# stm32f4breakout.net
KiCad netlist of a schematic drawn in EAGLE
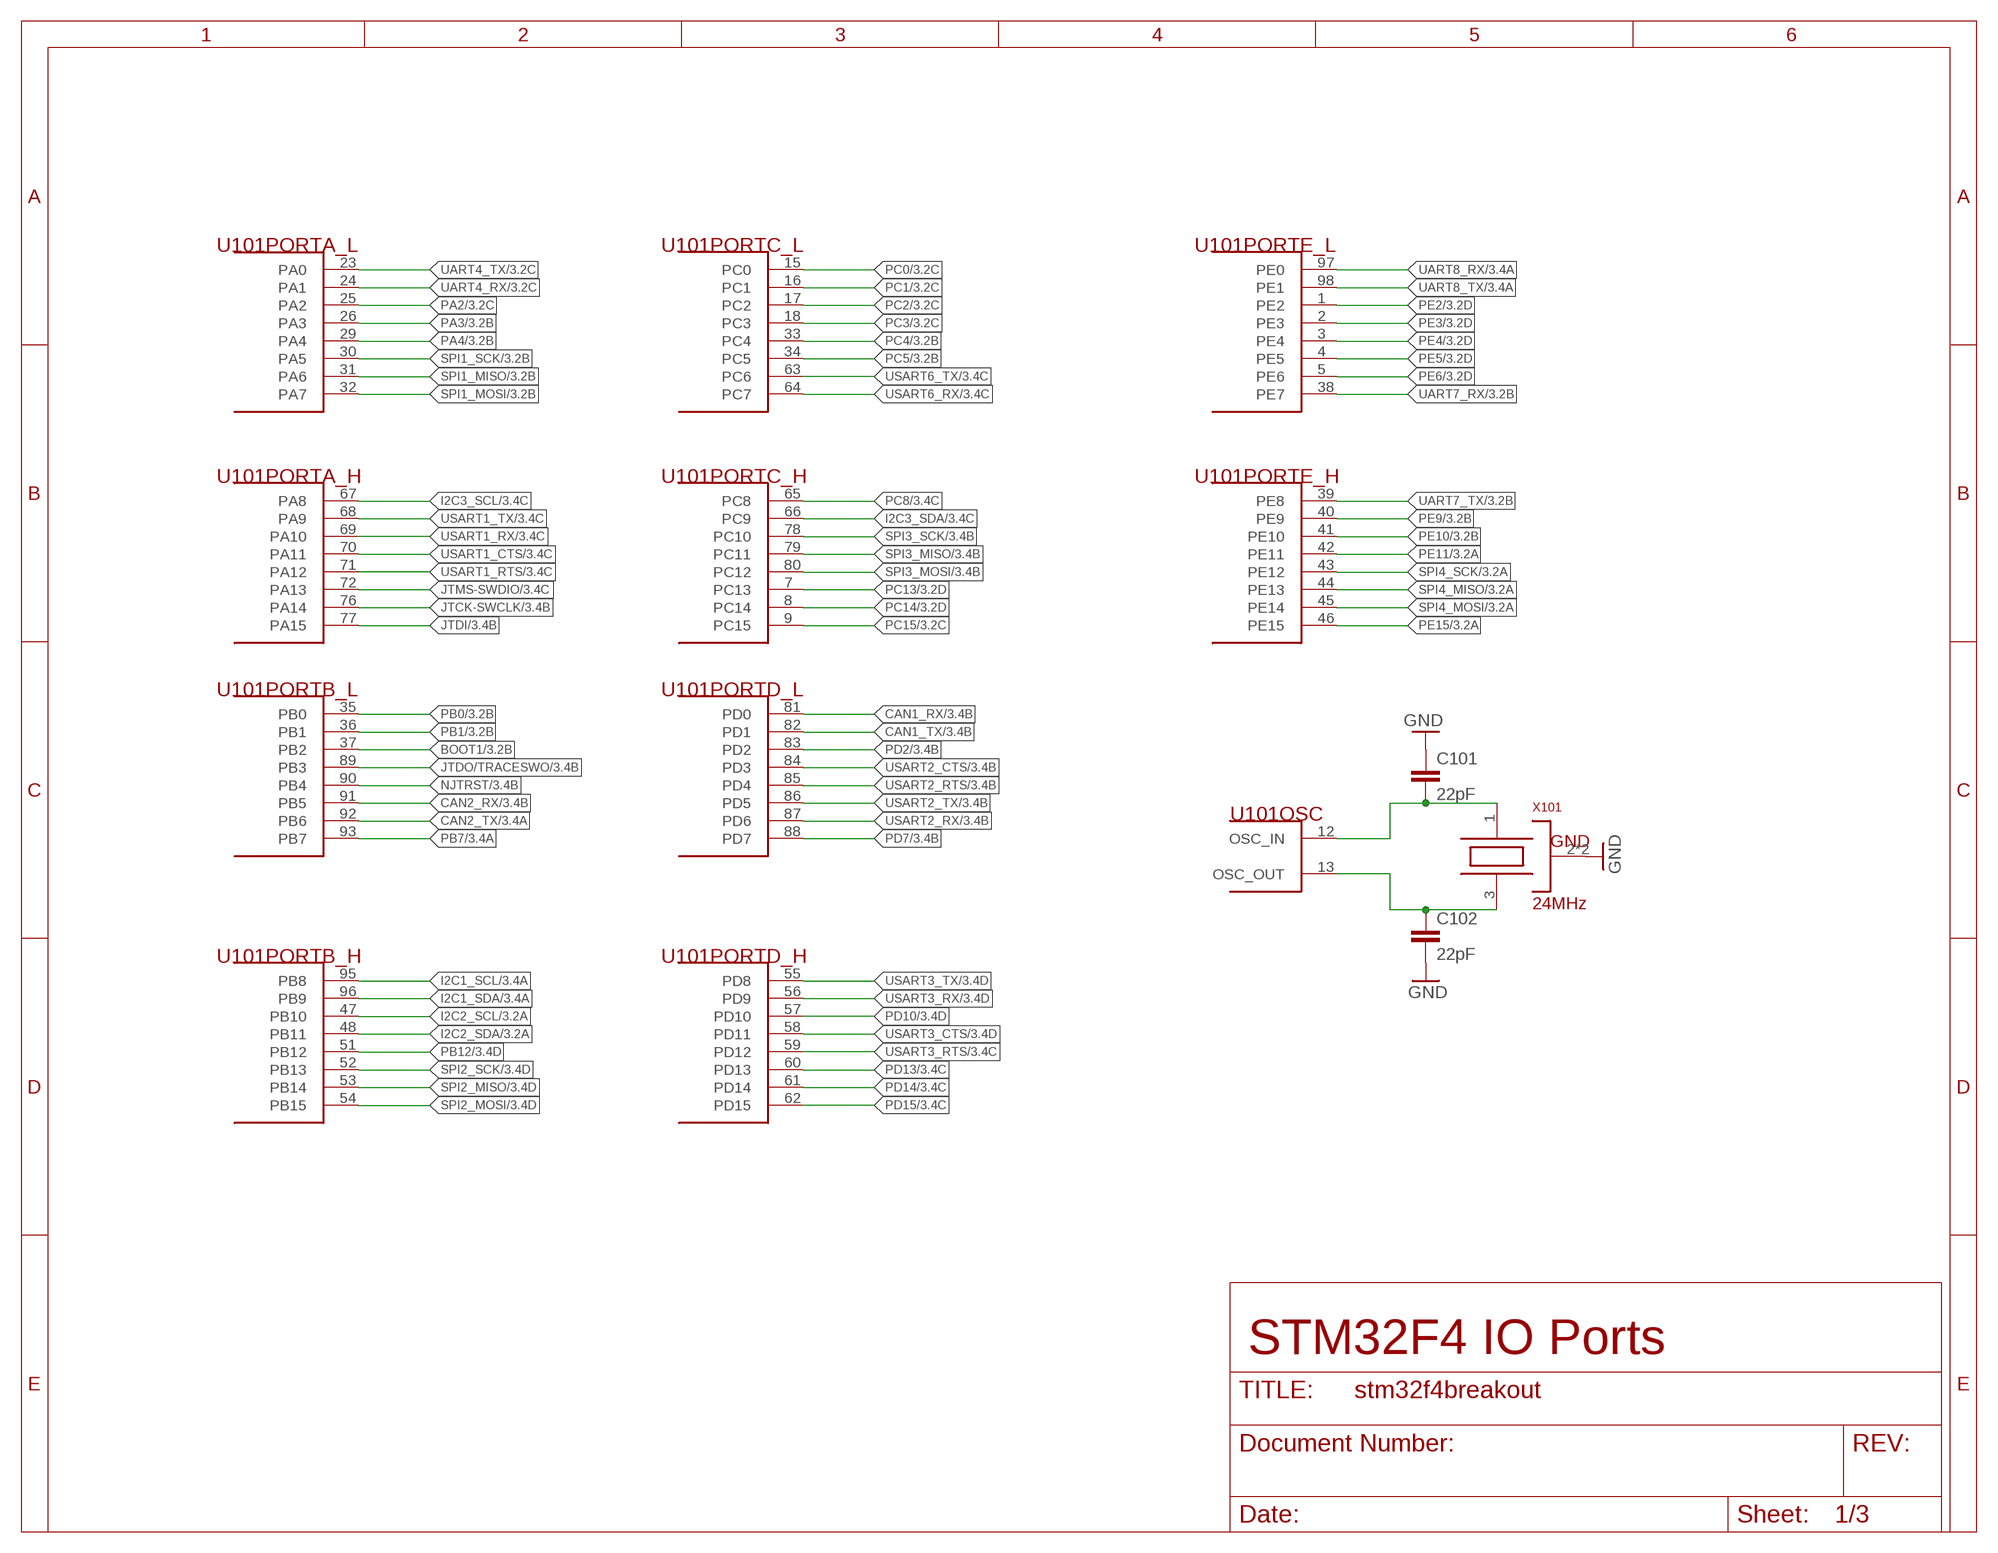
[diagram p0: schematic, sheet 1]
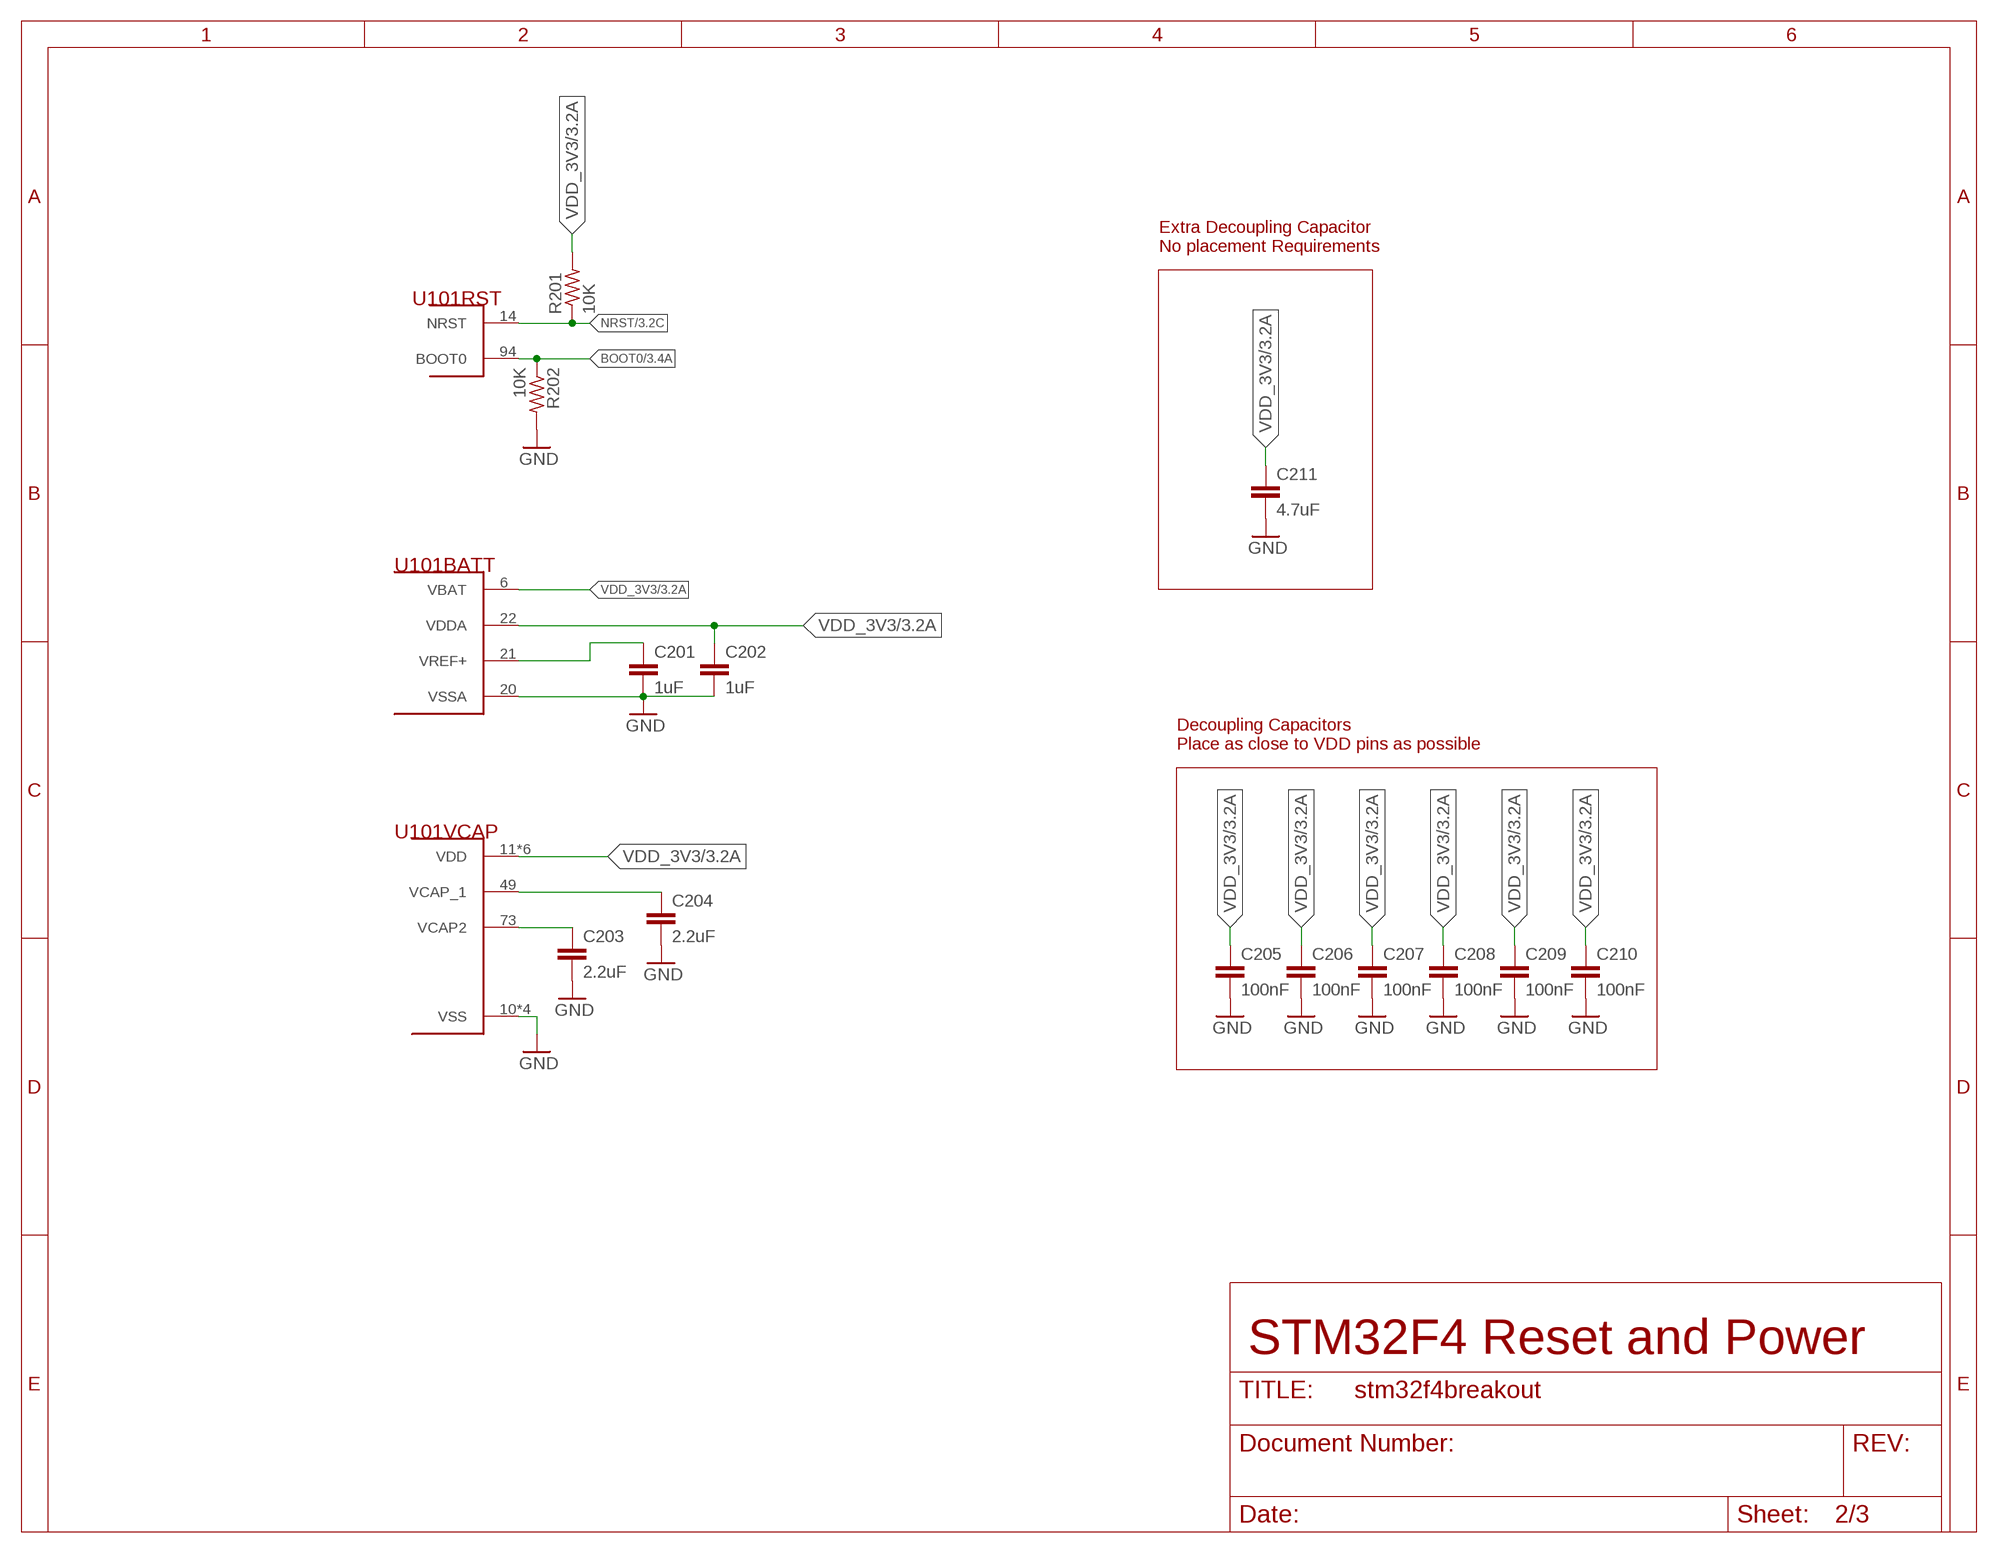
[diagram p1: schematic, sheet 2]
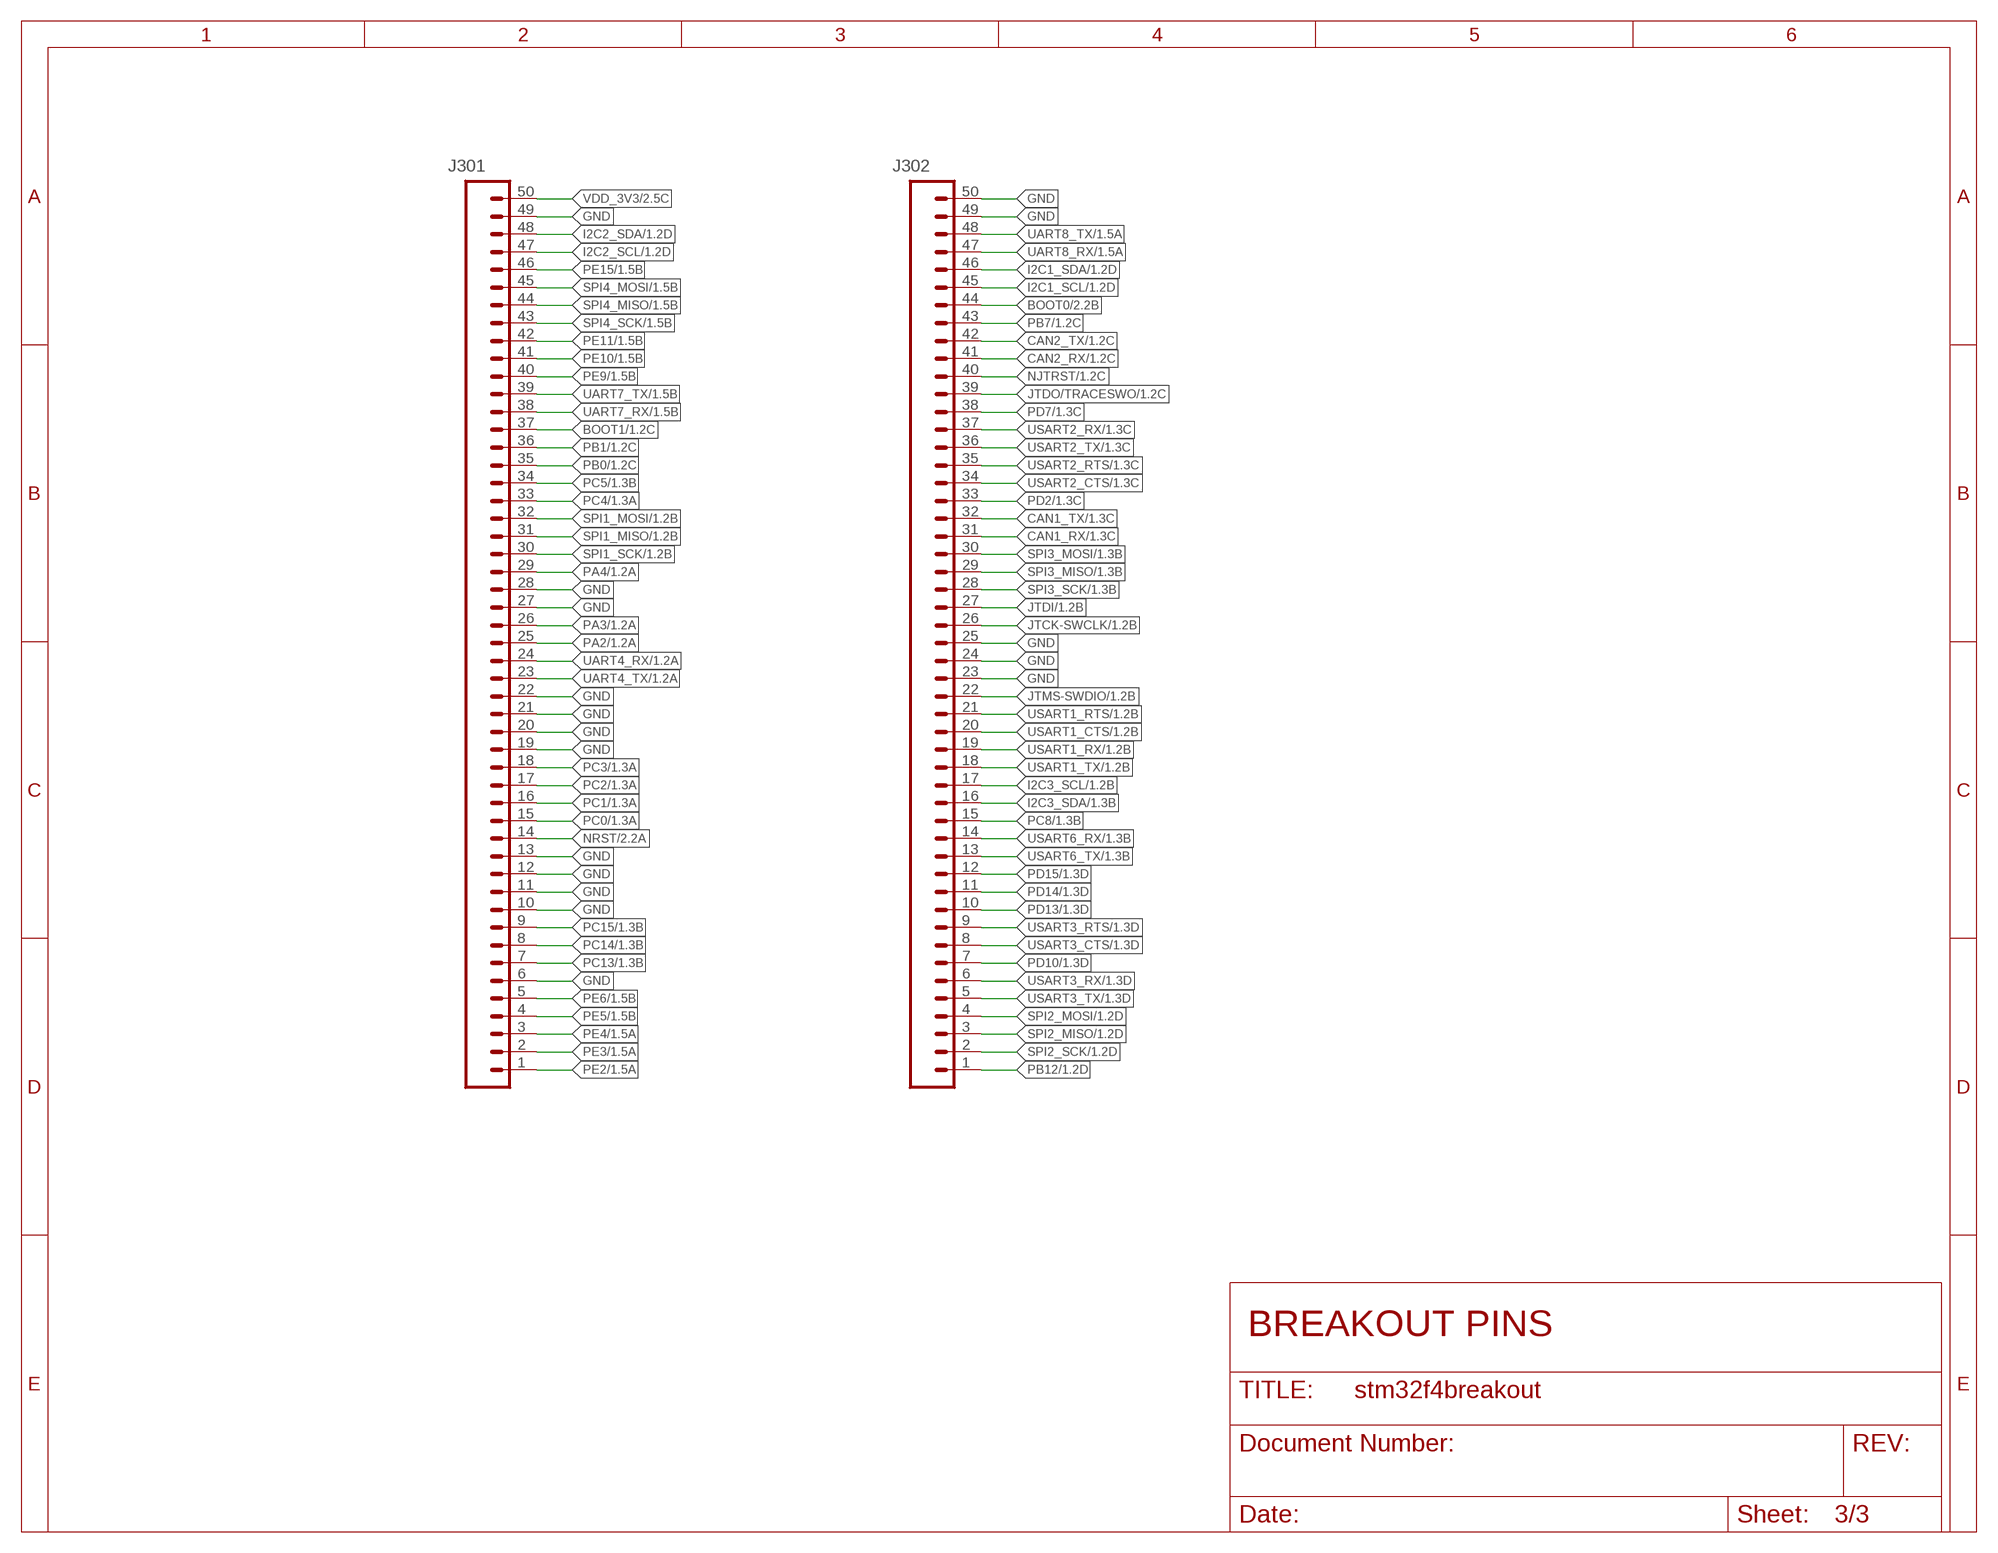
[diagram p2: schematic, sheet 3]

(export (version "E")
  (design (tool "Eeschema 10.0.6"))
  (components
    (comp (ref "C101")
      (value "22pF")
      (footprint "eagle-import:C0603")
      (libsource (lib "eagle-import") (part "C-EUC0603"))
    )
    (comp (ref "C102")
      (value "22pF")
      (footprint "eagle-import:C0603")
      (libsource (lib "eagle-import") (part "C-EUC0603"))
    )
    (comp (ref "U101")
      (value "STM32F427VGT6")
      (footprint "eagle-import:LQFP-100")
      (libsource (lib "eagle-import") (part "STM32F427VGT6"))
    )
    (comp (ref "X101")
      (value "24MHz")
      (footprint "eagle-import:OSC3.2X2.5")
      (libsource (lib "eagle-import") (part "OSCILLATOR"))
    )
    (comp (ref "C201")
      (value "1uF")
      (footprint "eagle-import:C0603")
      (libsource (lib "eagle-import") (part "C-EUC0603"))
    )
    (comp (ref "C202")
      (value "1uF")
      (footprint "eagle-import:C0603")
      (libsource (lib "eagle-import") (part "C-EUC0603"))
    )
    (comp (ref "C203")
      (value "2.2uF")
      (footprint "eagle-import:C0603")
      (libsource (lib "eagle-import") (part "C-EUC0603"))
    )
    (comp (ref "C204")
      (value "2.2uF")
      (footprint "eagle-import:C0603")
      (libsource (lib "eagle-import") (part "C-EUC0603"))
    )
    (comp (ref "C205")
      (value "100nF")
      (footprint "eagle-import:C0603")
      (libsource (lib "eagle-import") (part "C-EUC0603"))
    )
    (comp (ref "C206")
      (value "100nF")
      (footprint "eagle-import:C0603")
      (libsource (lib "eagle-import") (part "C-EUC0603"))
    )
    (comp (ref "C207")
      (value "100nF")
      (footprint "eagle-import:C0603")
      (libsource (lib "eagle-import") (part "C-EUC0603"))
    )
    (comp (ref "C208")
      (value "100nF")
      (footprint "eagle-import:C0603")
      (libsource (lib "eagle-import") (part "C-EUC0603"))
    )
    (comp (ref "C209")
      (value "100nF")
      (footprint "eagle-import:C0603")
      (libsource (lib "eagle-import") (part "C-EUC0603"))
    )
    (comp (ref "C210")
      (value "100nF")
      (footprint "eagle-import:C0603")
      (libsource (lib "eagle-import") (part "C-EUC0603"))
    )
    (comp (ref "C211")
      (value "4.7uF")
      (footprint "eagle-import:C0603")
      (libsource (lib "eagle-import") (part "C-EUC0603"))
    )
    (comp (ref "R201")
      (value "10K")
      (footprint "eagle-import:R0603")
      (libsource (lib "eagle-import") (part "R-US_R0603"))
    )
    (comp (ref "R202")
      (value "10K")
      (footprint "eagle-import:R0603")
      (libsource (lib "eagle-import") (part "R-US_R0603"))
    )
    (comp (ref "J301")
      (value "PINHD-1X50")
      (footprint "eagle-import:1X50")
      (libsource (lib "eagle-import") (part "PINHD-1X50"))
    )
    (comp (ref "J302")
      (value "PINHD-1X50")
      (footprint "eagle-import:1X50")
      (libsource (lib "eagle-import") (part "PINHD-1X50"))
    )
  )
  (nets
    (net (code "1") (name "BOOT0") (class "Default")
      (node (ref "J302") (pin "44") (pinfunction "44_44") (pintype "passive"))
      (node (ref "R202") (pin "1") (pinfunction "1_1") (pintype "passive"))
      (node (ref "U101") (pin "94") (pinfunction "BOOT0_94") (pintype "power_in"))
    )
    (net (code "2") (name "BOOT1") (class "Default")
      (node (ref "J301") (pin "37") (pinfunction "37_37") (pintype "passive"))
      (node (ref "U101") (pin "37") (pinfunction "PB2_37") (pintype "power_in"))
    )
    (net (code "3") (name "CAN1_RX") (class "Default")
      (node (ref "J302") (pin "31") (pinfunction "31_31") (pintype "passive"))
      (node (ref "U101") (pin "81") (pinfunction "PD0_81") (pintype "power_in"))
    )
    (net (code "4") (name "CAN1_TX") (class "Default")
      (node (ref "J302") (pin "32") (pinfunction "32_32") (pintype "passive"))
      (node (ref "U101") (pin "82") (pinfunction "PD1_82") (pintype "power_in"))
    )
    (net (code "5") (name "CAN2_RX") (class "Default")
      (node (ref "J302") (pin "41") (pinfunction "41_41") (pintype "passive"))
      (node (ref "U101") (pin "91") (pinfunction "PB5_91") (pintype "power_in"))
    )
    (net (code "6") (name "CAN2_TX") (class "Default")
      (node (ref "J302") (pin "42") (pinfunction "42_42") (pintype "passive"))
      (node (ref "U101") (pin "92") (pinfunction "PB6_92") (pintype "power_in"))
    )
    (net (code "7") (name "GND") (class "Default")
      (node (ref "C101") (pin "1") (pinfunction "1_1") (pintype "passive"))
      (node (ref "C102") (pin "2") (pinfunction "2_2") (pintype "passive"))
      (node (ref "C201") (pin "2") (pinfunction "2_2") (pintype "passive"))
      (node (ref "C202") (pin "2") (pinfunction "2_2") (pintype "passive"))
      (node (ref "C203") (pin "2") (pinfunction "2_2") (pintype "passive"))
      (node (ref "C204") (pin "2") (pinfunction "2_2") (pintype "passive"))
      (node (ref "C205") (pin "2") (pinfunction "2_2") (pintype "passive"))
      (node (ref "C206") (pin "2") (pinfunction "2_2") (pintype "passive"))
      (node (ref "C207") (pin "2") (pinfunction "2_2") (pintype "passive"))
      (node (ref "C208") (pin "2") (pinfunction "2_2") (pintype "passive"))
      (node (ref "C209") (pin "2") (pinfunction "2_2") (pintype "passive"))
      (node (ref "C210") (pin "2") (pinfunction "2_2") (pintype "passive"))
      (node (ref "C211") (pin "2") (pinfunction "2_2") (pintype "passive"))
      (node (ref "J301") (pin "10") (pinfunction "10_10") (pintype "passive"))
      (node (ref "J301") (pin "11") (pinfunction "11_11") (pintype "passive"))
      (node (ref "J301") (pin "12") (pinfunction "12_12") (pintype "passive"))
      (node (ref "J301") (pin "13") (pinfunction "13_13") (pintype "passive"))
      (node (ref "J301") (pin "19") (pinfunction "19_19") (pintype "passive"))
      (node (ref "J301") (pin "20") (pinfunction "20_20") (pintype "passive"))
      (node (ref "J301") (pin "21") (pinfunction "21_21") (pintype "passive"))
      (node (ref "J301") (pin "22") (pinfunction "22_22") (pintype "passive"))
      (node (ref "J301") (pin "27") (pinfunction "27_27") (pintype "passive"))
      (node (ref "J301") (pin "28") (pinfunction "28_28") (pintype "passive"))
      (node (ref "J301") (pin "49") (pinfunction "49_49") (pintype "passive"))
      (node (ref "J301") (pin "6") (pinfunction "6_6") (pintype "passive"))
      (node (ref "J302") (pin "23") (pinfunction "23_23") (pintype "passive"))
      (node (ref "J302") (pin "24") (pinfunction "24_24") (pintype "passive"))
      (node (ref "J302") (pin "25") (pinfunction "25_25") (pintype "passive"))
      (node (ref "J302") (pin "49") (pinfunction "49_49") (pintype "passive"))
      (node (ref "J302") (pin "50") (pinfunction "50_50") (pintype "passive"))
      (node (ref "R202") (pin "2") (pinfunction "2_2") (pintype "passive"))
      (node (ref "U101") (pin "10") (pinfunction "VSS_10") (pintype "power_in"))
      (node (ref "U101") (pin "20") (pinfunction "VSSA_20") (pintype "power_in"))
      (node (ref "U101") (pin "27") (pinfunction "VSS_27") (pintype "power_in"))
      (node (ref "U101") (pin "74") (pinfunction "VSS_74") (pintype "power_in"))
      (node (ref "U101") (pin "99") (pinfunction "VSS_99") (pintype "power_in"))
      (node (ref "X101") (pin "2") (pinfunction "GND_2") (pintype "power_in"))
      (node (ref "X101") (pin "4") (pinfunction "GND_4") (pintype "power_in"))
    )
    (net (code "8") (name "I2C1_SCL") (class "Default")
      (node (ref "J302") (pin "45") (pinfunction "45_45") (pintype "passive"))
      (node (ref "U101") (pin "95") (pinfunction "PB8_95") (pintype "power_in"))
    )
    (net (code "9") (name "I2C1_SDA") (class "Default")
      (node (ref "J302") (pin "46") (pinfunction "46_46") (pintype "passive"))
      (node (ref "U101") (pin "96") (pinfunction "PB9_96") (pintype "power_in"))
    )
    (net (code "10") (name "I2C2_SCL") (class "Default")
      (node (ref "J301") (pin "47") (pinfunction "47_47") (pintype "passive"))
      (node (ref "U101") (pin "47") (pinfunction "PB10_47") (pintype "power_in"))
    )
    (net (code "11") (name "I2C2_SDA") (class "Default")
      (node (ref "J301") (pin "48") (pinfunction "48_48") (pintype "passive"))
      (node (ref "U101") (pin "48") (pinfunction "PB11_48") (pintype "power_in"))
    )
    (net (code "12") (name "I2C3_SCL") (class "Default")
      (node (ref "J302") (pin "17") (pinfunction "17_17") (pintype "passive"))
      (node (ref "U101") (pin "67") (pinfunction "PA8_67") (pintype "power_in"))
    )
    (net (code "13") (name "I2C3_SDA") (class "Default")
      (node (ref "J302") (pin "16") (pinfunction "16_16") (pintype "passive"))
      (node (ref "U101") (pin "66") (pinfunction "PC9_66") (pintype "power_in"))
    )
    (net (code "14") (name "JTCK-SWCLK") (class "Default")
      (node (ref "J302") (pin "26") (pinfunction "26_26") (pintype "passive"))
      (node (ref "U101") (pin "76") (pinfunction "PA14_76") (pintype "power_in"))
    )
    (net (code "15") (name "JTDI") (class "Default")
      (node (ref "J302") (pin "27") (pinfunction "27_27") (pintype "passive"))
      (node (ref "U101") (pin "77") (pinfunction "PA15_77") (pintype "power_in"))
    )
    (net (code "16") (name "JTDO{slash}TRACESWO") (class "Default")
      (node (ref "J302") (pin "39") (pinfunction "39_39") (pintype "passive"))
      (node (ref "U101") (pin "89") (pinfunction "PB3_89") (pintype "power_in"))
    )
    (net (code "17") (name "JTMS-SWDIO") (class "Default")
      (node (ref "J302") (pin "22") (pinfunction "22_22") (pintype "passive"))
      (node (ref "U101") (pin "72") (pinfunction "PA13_72") (pintype "power_in"))
    )
    (net (code "18") (name "NJTRST") (class "Default")
      (node (ref "J302") (pin "40") (pinfunction "40_40") (pintype "passive"))
      (node (ref "U101") (pin "90") (pinfunction "PB4_90") (pintype "power_in"))
    )
    (net (code "19") (name "NRST") (class "Default")
      (node (ref "J301") (pin "14") (pinfunction "14_14") (pintype "passive"))
      (node (ref "R201") (pin "1") (pinfunction "1_1") (pintype "passive"))
      (node (ref "U101") (pin "14") (pinfunction "NRST_14") (pintype "power_in"))
    )
    (net (code "20") (name "Net-(U101B-OSC_IN)") (class "Default")
      (node (ref "C101") (pin "2") (pinfunction "2_2") (pintype "passive"))
      (node (ref "U101") (pin "12") (pinfunction "OSC_IN_12") (pintype "power_in"))
      (node (ref "X101") (pin "1") (pinfunction "OSC1_1") (pintype "bidirectional"))
    )
    (net (code "21") (name "Net-(U101B-OSC_OUT)") (class "Default")
      (node (ref "C102") (pin "1") (pinfunction "1_1") (pintype "passive"))
      (node (ref "U101") (pin "13") (pinfunction "OSC_OUT_13") (pintype "power_in"))
      (node (ref "X101") (pin "3") (pinfunction "OSC2_3") (pintype "bidirectional"))
    )
    (net (code "22") (name "Net-(U101N-VCAP2)") (class "Default")
      (node (ref "C203") (pin "1") (pinfunction "1_1") (pintype "passive"))
      (node (ref "U101") (pin "73") (pinfunction "VCAP2_73") (pintype "power_in"))
    )
    (net (code "23") (name "Net-(U101N-VCAP_1)") (class "Default")
      (node (ref "C204") (pin "1") (pinfunction "1_1") (pintype "passive"))
      (node (ref "U101") (pin "49") (pinfunction "VCAP_1_49") (pintype "power_in"))
    )
    (net (code "24") (name "PA2") (class "Default")
      (node (ref "J301") (pin "25") (pinfunction "25_25") (pintype "passive"))
      (node (ref "U101") (pin "25") (pinfunction "PA2_25") (pintype "power_in"))
    )
    (net (code "25") (name "PA3") (class "Default")
      (node (ref "J301") (pin "26") (pinfunction "26_26") (pintype "passive"))
      (node (ref "U101") (pin "26") (pinfunction "PA3_26") (pintype "power_in"))
    )
    (net (code "26") (name "PA4") (class "Default")
      (node (ref "J301") (pin "29") (pinfunction "29_29") (pintype "passive"))
      (node (ref "U101") (pin "29") (pinfunction "PA4_29") (pintype "power_in"))
    )
    (net (code "27") (name "PB0") (class "Default")
      (node (ref "J301") (pin "35") (pinfunction "35_35") (pintype "passive"))
      (node (ref "U101") (pin "35") (pinfunction "PB0_35") (pintype "power_in"))
    )
    (net (code "28") (name "PB1") (class "Default")
      (node (ref "J301") (pin "36") (pinfunction "36_36") (pintype "passive"))
      (node (ref "U101") (pin "36") (pinfunction "PB1_36") (pintype "power_in"))
    )
    (net (code "29") (name "PB7") (class "Default")
      (node (ref "J302") (pin "43") (pinfunction "43_43") (pintype "passive"))
      (node (ref "U101") (pin "93") (pinfunction "PB7_93") (pintype "power_in"))
    )
    (net (code "30") (name "PB12") (class "Default")
      (node (ref "J302") (pin "1") (pinfunction "1_1") (pintype "passive"))
      (node (ref "U101") (pin "51") (pinfunction "PB12_51") (pintype "power_in"))
    )
    (net (code "31") (name "PC0") (class "Default")
      (node (ref "J301") (pin "15") (pinfunction "15_15") (pintype "passive"))
      (node (ref "U101") (pin "15") (pinfunction "PC0_15") (pintype "power_in"))
    )
    (net (code "32") (name "PC1") (class "Default")
      (node (ref "J301") (pin "16") (pinfunction "16_16") (pintype "passive"))
      (node (ref "U101") (pin "16") (pinfunction "PC1_16") (pintype "power_in"))
    )
    (net (code "33") (name "PC2") (class "Default")
      (node (ref "J301") (pin "17") (pinfunction "17_17") (pintype "passive"))
      (node (ref "U101") (pin "17") (pinfunction "PC2_17") (pintype "power_in"))
    )
    (net (code "34") (name "PC3") (class "Default")
      (node (ref "J301") (pin "18") (pinfunction "18_18") (pintype "passive"))
      (node (ref "U101") (pin "18") (pinfunction "PC3_18") (pintype "power_in"))
    )
    (net (code "35") (name "PC4") (class "Default")
      (node (ref "J301") (pin "33") (pinfunction "33_33") (pintype "passive"))
      (node (ref "U101") (pin "33") (pinfunction "PC4_33") (pintype "power_in"))
    )
    (net (code "36") (name "PC5") (class "Default")
      (node (ref "J301") (pin "34") (pinfunction "34_34") (pintype "passive"))
      (node (ref "U101") (pin "34") (pinfunction "PC5_34") (pintype "power_in"))
    )
    (net (code "37") (name "PC8") (class "Default")
      (node (ref "J302") (pin "15") (pinfunction "15_15") (pintype "passive"))
      (node (ref "U101") (pin "65") (pinfunction "PC8_65") (pintype "power_in"))
    )
    (net (code "38") (name "PC13") (class "Default")
      (node (ref "J301") (pin "7") (pinfunction "7_7") (pintype "passive"))
      (node (ref "U101") (pin "7") (pinfunction "PC13_7") (pintype "power_in"))
    )
    (net (code "39") (name "PC14") (class "Default")
      (node (ref "J301") (pin "8") (pinfunction "8_8") (pintype "passive"))
      (node (ref "U101") (pin "8") (pinfunction "PC14_8") (pintype "power_in"))
    )
    (net (code "40") (name "PC15") (class "Default")
      (node (ref "J301") (pin "9") (pinfunction "9_9") (pintype "passive"))
      (node (ref "U101") (pin "9") (pinfunction "PC15_9") (pintype "power_in"))
    )
    (net (code "41") (name "PD2") (class "Default")
      (node (ref "J302") (pin "33") (pinfunction "33_33") (pintype "passive"))
      (node (ref "U101") (pin "83") (pinfunction "PD2_83") (pintype "power_in"))
    )
    (net (code "42") (name "PD7") (class "Default")
      (node (ref "J302") (pin "38") (pinfunction "38_38") (pintype "passive"))
      (node (ref "U101") (pin "88") (pinfunction "PD7_88") (pintype "power_in"))
    )
    (net (code "43") (name "PD10") (class "Default")
      (node (ref "J302") (pin "7") (pinfunction "7_7") (pintype "passive"))
      (node (ref "U101") (pin "57") (pinfunction "PD10_57") (pintype "power_in"))
    )
    (net (code "44") (name "PD13") (class "Default")
      (node (ref "J302") (pin "10") (pinfunction "10_10") (pintype "passive"))
      (node (ref "U101") (pin "60") (pinfunction "PD13_60") (pintype "power_in"))
    )
    (net (code "45") (name "PD14") (class "Default")
      (node (ref "J302") (pin "11") (pinfunction "11_11") (pintype "passive"))
      (node (ref "U101") (pin "61") (pinfunction "PD14_61") (pintype "power_in"))
    )
    (net (code "46") (name "PD15") (class "Default")
      (node (ref "J302") (pin "12") (pinfunction "12_12") (pintype "passive"))
      (node (ref "U101") (pin "62") (pinfunction "PD15_62") (pintype "power_in"))
    )
    (net (code "47") (name "PE2") (class "Default")
      (node (ref "J301") (pin "1") (pinfunction "1_1") (pintype "passive"))
      (node (ref "U101") (pin "1") (pinfunction "PE2_1") (pintype "power_in"))
    )
    (net (code "48") (name "PE3") (class "Default")
      (node (ref "J301") (pin "2") (pinfunction "2_2") (pintype "passive"))
      (node (ref "U101") (pin "2") (pinfunction "PE3_2") (pintype "power_in"))
    )
    (net (code "49") (name "PE4") (class "Default")
      (node (ref "J301") (pin "3") (pinfunction "3_3") (pintype "passive"))
      (node (ref "U101") (pin "3") (pinfunction "PE4_3") (pintype "power_in"))
    )
    (net (code "50") (name "PE5") (class "Default")
      (node (ref "J301") (pin "4") (pinfunction "4_4") (pintype "passive"))
      (node (ref "U101") (pin "4") (pinfunction "PE5_4") (pintype "power_in"))
    )
    (net (code "51") (name "PE6") (class "Default")
      (node (ref "J301") (pin "5") (pinfunction "5_5") (pintype "passive"))
      (node (ref "U101") (pin "5") (pinfunction "PE6_5") (pintype "power_in"))
    )
    (net (code "52") (name "PE9") (class "Default")
      (node (ref "J301") (pin "40") (pinfunction "40_40") (pintype "passive"))
      (node (ref "U101") (pin "40") (pinfunction "PE9_40") (pintype "power_in"))
    )
    (net (code "53") (name "PE10") (class "Default")
      (node (ref "J301") (pin "41") (pinfunction "41_41") (pintype "passive"))
      (node (ref "U101") (pin "41") (pinfunction "PE10_41") (pintype "power_in"))
    )
    (net (code "54") (name "PE11") (class "Default")
      (node (ref "J301") (pin "42") (pinfunction "42_42") (pintype "passive"))
      (node (ref "U101") (pin "42") (pinfunction "PE11_42") (pintype "power_in"))
    )
    (net (code "55") (name "PE15") (class "Default")
      (node (ref "J301") (pin "46") (pinfunction "46_46") (pintype "passive"))
      (node (ref "U101") (pin "46") (pinfunction "PE15_46") (pintype "power_in"))
    )
    (net (code "56") (name "SPI1_MISO") (class "Default")
      (node (ref "J301") (pin "31") (pinfunction "31_31") (pintype "passive"))
      (node (ref "U101") (pin "31") (pinfunction "PA6_31") (pintype "power_in"))
    )
    (net (code "57") (name "SPI1_MOSI") (class "Default")
      (node (ref "J301") (pin "32") (pinfunction "32_32") (pintype "passive"))
      (node (ref "U101") (pin "32") (pinfunction "PA7_32") (pintype "power_in"))
    )
    (net (code "58") (name "SPI1_SCK") (class "Default")
      (node (ref "J301") (pin "30") (pinfunction "30_30") (pintype "passive"))
      (node (ref "U101") (pin "30") (pinfunction "PA5_30") (pintype "power_in"))
    )
    (net (code "59") (name "SPI2_MISO") (class "Default")
      (node (ref "J302") (pin "3") (pinfunction "3_3") (pintype "passive"))
      (node (ref "U101") (pin "53") (pinfunction "PB14_53") (pintype "power_in"))
    )
    (net (code "60") (name "SPI2_MOSI") (class "Default")
      (node (ref "J302") (pin "4") (pinfunction "4_4") (pintype "passive"))
      (node (ref "U101") (pin "54") (pinfunction "PB15_54") (pintype "power_in"))
    )
    (net (code "61") (name "SPI2_SCK") (class "Default")
      (node (ref "J302") (pin "2") (pinfunction "2_2") (pintype "passive"))
      (node (ref "U101") (pin "52") (pinfunction "PB13_52") (pintype "power_in"))
    )
    (net (code "62") (name "SPI3_MISO") (class "Default")
      (node (ref "J302") (pin "29") (pinfunction "29_29") (pintype "passive"))
      (node (ref "U101") (pin "79") (pinfunction "PC11_79") (pintype "power_in"))
    )
    (net (code "63") (name "SPI3_MOSI") (class "Default")
      (node (ref "J302") (pin "30") (pinfunction "30_30") (pintype "passive"))
      (node (ref "U101") (pin "80") (pinfunction "PC12_80") (pintype "power_in"))
    )
    (net (code "64") (name "SPI3_SCK") (class "Default")
      (node (ref "J302") (pin "28") (pinfunction "28_28") (pintype "passive"))
      (node (ref "U101") (pin "78") (pinfunction "PC10_78") (pintype "power_in"))
    )
    (net (code "65") (name "SPI4_MISO") (class "Default")
      (node (ref "J301") (pin "44") (pinfunction "44_44") (pintype "passive"))
      (node (ref "U101") (pin "44") (pinfunction "PE13_44") (pintype "power_in"))
    )
    (net (code "66") (name "SPI4_MOSI") (class "Default")
      (node (ref "J301") (pin "45") (pinfunction "45_45") (pintype "passive"))
      (node (ref "U101") (pin "45") (pinfunction "PE14_45") (pintype "power_in"))
    )
    (net (code "67") (name "SPI4_SCK") (class "Default")
      (node (ref "J301") (pin "43") (pinfunction "43_43") (pintype "passive"))
      (node (ref "U101") (pin "43") (pinfunction "PE12_43") (pintype "power_in"))
    )
    (net (code "68") (name "UART4_RX") (class "Default")
      (node (ref "J301") (pin "24") (pinfunction "24_24") (pintype "passive"))
      (node (ref "U101") (pin "24") (pinfunction "PA1_24") (pintype "power_in"))
    )
    (net (code "69") (name "UART4_TX") (class "Default")
      (node (ref "J301") (pin "23") (pinfunction "23_23") (pintype "passive"))
      (node (ref "U101") (pin "23") (pinfunction "PA0_23") (pintype "power_in"))
    )
    (net (code "70") (name "UART7_RX") (class "Default")
      (node (ref "J301") (pin "38") (pinfunction "38_38") (pintype "passive"))
      (node (ref "U101") (pin "38") (pinfunction "PE7_38") (pintype "power_in"))
    )
    (net (code "71") (name "UART7_TX") (class "Default")
      (node (ref "J301") (pin "39") (pinfunction "39_39") (pintype "passive"))
      (node (ref "U101") (pin "39") (pinfunction "PE8_39") (pintype "power_in"))
    )
    (net (code "72") (name "UART8_RX") (class "Default")
      (node (ref "J302") (pin "47") (pinfunction "47_47") (pintype "passive"))
      (node (ref "U101") (pin "97") (pinfunction "PE0_97") (pintype "power_in"))
    )
    (net (code "73") (name "UART8_TX") (class "Default")
      (node (ref "J302") (pin "48") (pinfunction "48_48") (pintype "passive"))
      (node (ref "U101") (pin "98") (pinfunction "PE1_98") (pintype "power_in"))
    )
    (net (code "74") (name "USART1_CTS") (class "Default")
      (node (ref "J302") (pin "20") (pinfunction "20_20") (pintype "passive"))
      (node (ref "U101") (pin "70") (pinfunction "PA11_70") (pintype "power_in"))
    )
    (net (code "75") (name "USART1_RTS") (class "Default")
      (node (ref "J302") (pin "21") (pinfunction "21_21") (pintype "passive"))
      (node (ref "U101") (pin "71") (pinfunction "PA12_71") (pintype "power_in"))
    )
    (net (code "76") (name "USART1_RX") (class "Default")
      (node (ref "J302") (pin "19") (pinfunction "19_19") (pintype "passive"))
      (node (ref "U101") (pin "69") (pinfunction "PA10_69") (pintype "power_in"))
    )
    (net (code "77") (name "USART1_TX") (class "Default")
      (node (ref "J302") (pin "18") (pinfunction "18_18") (pintype "passive"))
      (node (ref "U101") (pin "68") (pinfunction "PA9_68") (pintype "power_in"))
    )
    (net (code "78") (name "USART2_CTS") (class "Default")
      (node (ref "J302") (pin "34") (pinfunction "34_34") (pintype "passive"))
      (node (ref "U101") (pin "84") (pinfunction "PD3_84") (pintype "power_in"))
    )
    (net (code "79") (name "USART2_RTS") (class "Default")
      (node (ref "J302") (pin "35") (pinfunction "35_35") (pintype "passive"))
      (node (ref "U101") (pin "85") (pinfunction "PD4_85") (pintype "power_in"))
    )
    (net (code "80") (name "USART2_RX") (class "Default")
      (node (ref "J302") (pin "37") (pinfunction "37_37") (pintype "passive"))
      (node (ref "U101") (pin "87") (pinfunction "PD6_87") (pintype "power_in"))
    )
    (net (code "81") (name "USART2_TX") (class "Default")
      (node (ref "J302") (pin "36") (pinfunction "36_36") (pintype "passive"))
      (node (ref "U101") (pin "86") (pinfunction "PD5_86") (pintype "power_in"))
    )
    (net (code "82") (name "USART3_CTS") (class "Default")
      (node (ref "J302") (pin "8") (pinfunction "8_8") (pintype "passive"))
      (node (ref "U101") (pin "58") (pinfunction "PD11_58") (pintype "power_in"))
    )
    (net (code "83") (name "USART3_RTS") (class "Default")
      (node (ref "J302") (pin "9") (pinfunction "9_9") (pintype "passive"))
      (node (ref "U101") (pin "59") (pinfunction "PD12_59") (pintype "power_in"))
    )
    (net (code "84") (name "USART3_RX") (class "Default")
      (node (ref "J302") (pin "6") (pinfunction "6_6") (pintype "passive"))
      (node (ref "U101") (pin "56") (pinfunction "PD9_56") (pintype "power_in"))
    )
    (net (code "85") (name "USART3_TX") (class "Default")
      (node (ref "J302") (pin "5") (pinfunction "5_5") (pintype "passive"))
      (node (ref "U101") (pin "55") (pinfunction "PD8_55") (pintype "power_in"))
    )
    (net (code "86") (name "USART6_RX") (class "Default")
      (node (ref "J302") (pin "14") (pinfunction "14_14") (pintype "passive"))
      (node (ref "U101") (pin "64") (pinfunction "PC7_64") (pintype "power_in"))
    )
    (net (code "87") (name "USART6_TX") (class "Default")
      (node (ref "J302") (pin "13") (pinfunction "13_13") (pintype "passive"))
      (node (ref "U101") (pin "63") (pinfunction "PC6_63") (pintype "power_in"))
    )
    (net (code "88") (name "VDD_3V3") (class "Default")
      (node (ref "C201") (pin "1") (pinfunction "1_1") (pintype "passive"))
      (node (ref "C202") (pin "1") (pinfunction "1_1") (pintype "passive"))
      (node (ref "C205") (pin "1") (pinfunction "1_1") (pintype "passive"))
      (node (ref "C206") (pin "1") (pinfunction "1_1") (pintype "passive"))
      (node (ref "C207") (pin "1") (pinfunction "1_1") (pintype "passive"))
      (node (ref "C208") (pin "1") (pinfunction "1_1") (pintype "passive"))
      (node (ref "C209") (pin "1") (pinfunction "1_1") (pintype "passive"))
      (node (ref "C210") (pin "1") (pinfunction "1_1") (pintype "passive"))
      (node (ref "C211") (pin "1") (pinfunction "1_1") (pintype "passive"))
      (node (ref "J301") (pin "50") (pinfunction "50_50") (pintype "passive"))
      (node (ref "R201") (pin "2") (pinfunction "2_2") (pintype "passive"))
      (node (ref "U101") (pin "100") (pinfunction "VDD_100") (pintype "power_in"))
      (node (ref "U101") (pin "11") (pinfunction "VDD_11") (pintype "power_in"))
      (node (ref "U101") (pin "19") (pinfunction "VDD_19") (pintype "power_in"))
      (node (ref "U101") (pin "21") (pinfunction "VREF+_21") (pintype "power_in"))
      (node (ref "U101") (pin "22") (pinfunction "VDDA_22") (pintype "power_in"))
      (node (ref "U101") (pin "28") (pinfunction "VDD_28") (pintype "power_in"))
      (node (ref "U101") (pin "50") (pinfunction "VDD_50") (pintype "power_in"))
      (node (ref "U101") (pin "6") (pinfunction "VBAT_6") (pintype "power_in"))
      (node (ref "U101") (pin "75") (pinfunction "VDD_75") (pintype "power_in"))
    )
  )
)
